# Module_Output_Connector.net
KiCad netlist of a schematic drawn in Altium Designer
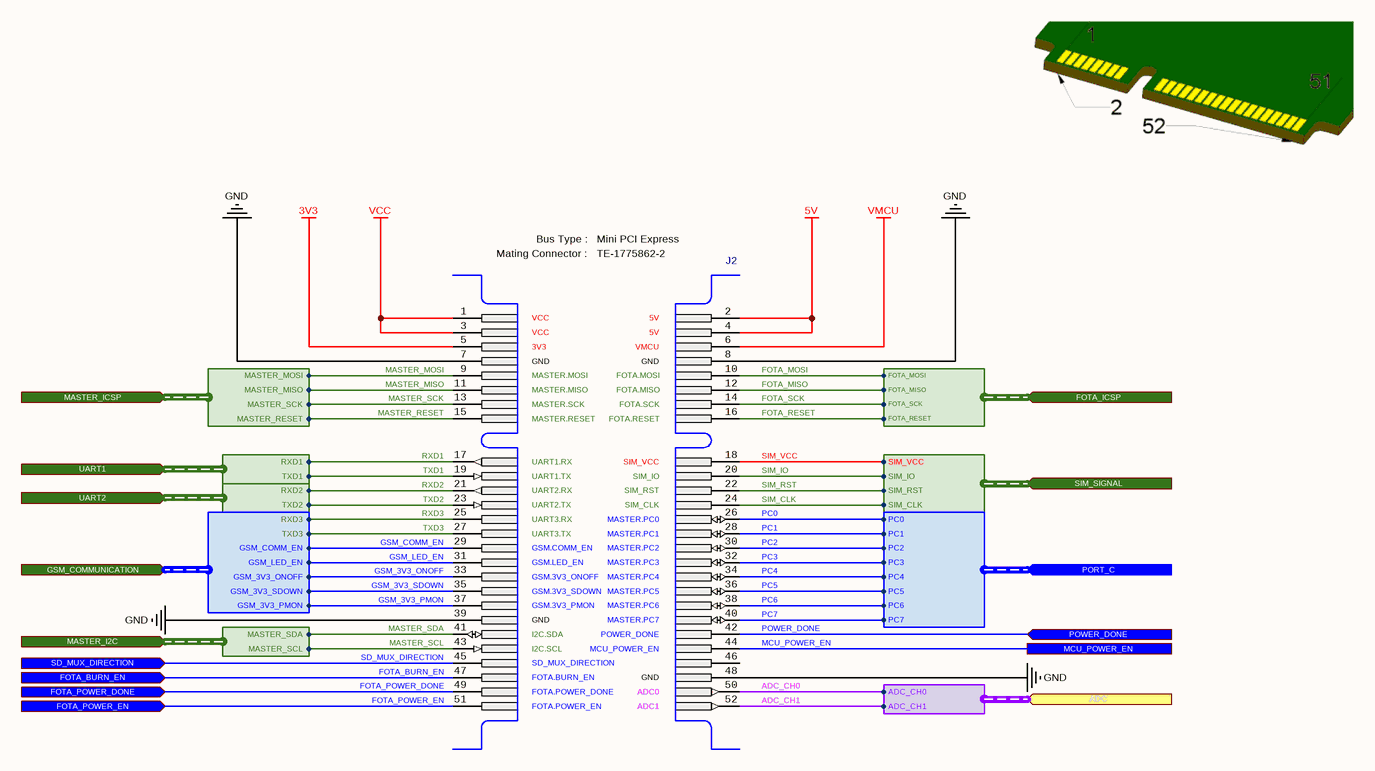
[diagram p0: Module Output Connector.SchDoc]

(export (version "E")
  (design (tool "Eeschema 10.0.6"))
  (components
    (comp (ref "J2")
      (value "Mini PCI Express Gold Finger")
      (footprint "PCB - Mini PCI Express")
      (fields (field (name "BUS TYPE") "Mini PCI Express") (field (name "MATING CONNECTOR") "TE-1775862-2"))
      (libsource (lib "Ovoo_Library") (part "PCB - Mini PCI Express & MSATA"))
    )
  )
  (nets
    (net (code "10") (name "/ADC_CH0") (class "Default")
      (node (ref "J2") (pin "50") (pinfunction "Pin-50_50") (pintype "output"))
    )
    (net (code "11") (name "/ADC_CH1") (class "Default")
      (node (ref "J2") (pin "52") (pinfunction "Pin-52_52") (pintype "output"))
    )
    (net (code "12") (name "/FOTA_BURN_EN") (class "Default")
      (node (ref "J2") (pin "47") (pinfunction "Pin-47_47") (pintype "passive"))
    )
    (net (code "13") (name "/FOTA_MISO") (class "Default")
      (node (ref "J2") (pin "12") (pinfunction "Pin-12_12") (pintype "passive"))
    )
    (net (code "14") (name "/FOTA_MOSI") (class "Default")
      (node (ref "J2") (pin "10") (pinfunction "Pin-10_10") (pintype "passive"))
    )
    (net (code "15") (name "/FOTA_POWER_DONE") (class "Default")
      (node (ref "J2") (pin "49") (pinfunction "Pin-49_49") (pintype "passive"))
    )
    (net (code "16") (name "/FOTA_POWER_EN") (class "Default")
      (node (ref "J2") (pin "51") (pinfunction "Pin-51_51") (pintype "passive"))
    )
    (net (code "17") (name "/FOTA_RESET") (class "Default")
      (node (ref "J2") (pin "16") (pinfunction "Pin-16_16") (pintype "passive"))
    )
    (net (code "18") (name "/FOTA_SCK") (class "Default")
      (node (ref "J2") (pin "14") (pinfunction "Pin-14_14") (pintype "passive"))
    )
    (net (code "19") (name "/GSM_3V3_ONOFF") (class "Default")
      (node (ref "J2") (pin "33") (pinfunction "Pin-33_33") (pintype "passive"))
    )
    (net (code "20") (name "/GSM_3V3_PMON") (class "Default")
      (node (ref "J2") (pin "37") (pinfunction "Pin-37_37") (pintype "passive"))
    )
    (net (code "21") (name "/GSM_3V3_SDOWN") (class "Default")
      (node (ref "J2") (pin "35") (pinfunction "Pin-35_35") (pintype "passive"))
    )
    (net (code "22") (name "/GSM_COMM_EN") (class "Default")
      (node (ref "J2") (pin "29") (pinfunction "Pin-29_29") (pintype "passive"))
    )
    (net (code "23") (name "/GSM_LED_EN") (class "Default")
      (node (ref "J2") (pin "31") (pinfunction "Pin-31_31") (pintype "passive"))
    )
    (net (code "24") (name "/MASTER_MISO") (class "Default")
      (node (ref "J2") (pin "11") (pinfunction "Pin-11_11") (pintype "passive"))
    )
    (net (code "25") (name "/MASTER_MOSI") (class "Default")
      (node (ref "J2") (pin "9") (pinfunction "Pin-9_9") (pintype "passive"))
    )
    (net (code "26") (name "/MASTER_RESET") (class "Default")
      (node (ref "J2") (pin "15") (pinfunction "Pin-15_15") (pintype "passive"))
    )
    (net (code "27") (name "/MASTER_SCK") (class "Default")
      (node (ref "J2") (pin "13") (pinfunction "Pin-13_13") (pintype "passive"))
    )
    (net (code "28") (name "/MASTER_SCL") (class "Default")
      (node (ref "J2") (pin "43") (pinfunction "Pin-43_43") (pintype "input"))
    )
    (net (code "29") (name "/MASTER_SDA") (class "Default")
      (node (ref "J2") (pin "41") (pinfunction "Pin-41_41") (pintype "bidirectional"))
    )
    (net (code "30") (name "/MCU_POWER_EN") (class "Default")
      (node (ref "J2") (pin "44") (pinfunction "Pin-44_44") (pintype "passive"))
    )
    (net (code "31") (name "/PC0") (class "Default")
      (node (ref "J2") (pin "26") (pinfunction "Pin-26_26") (pintype "bidirectional"))
    )
    (net (code "32") (name "/PC1") (class "Default")
      (node (ref "J2") (pin "28") (pinfunction "Pin-28_28") (pintype "bidirectional"))
    )
    (net (code "33") (name "/PC2") (class "Default")
      (node (ref "J2") (pin "30") (pinfunction "Pin-30_30") (pintype "bidirectional"))
    )
    (net (code "34") (name "/PC3") (class "Default")
      (node (ref "J2") (pin "32") (pinfunction "Pin-32_32") (pintype "bidirectional"))
    )
    (net (code "35") (name "/PC4") (class "Default")
      (node (ref "J2") (pin "34") (pinfunction "Pin-34_34") (pintype "bidirectional"))
    )
    (net (code "36") (name "/PC5") (class "Default")
      (node (ref "J2") (pin "36") (pinfunction "Pin-36_36") (pintype "bidirectional"))
    )
    (net (code "37") (name "/PC6") (class "Default")
      (node (ref "J2") (pin "38") (pinfunction "Pin-38_38") (pintype "bidirectional"))
    )
    (net (code "38") (name "/PC7") (class "Default")
      (node (ref "J2") (pin "40") (pinfunction "Pin-40_40") (pintype "bidirectional"))
    )
    (net (code "39") (name "/POWER_DONE") (class "Default")
      (node (ref "J2") (pin "42") (pinfunction "Pin-42_42") (pintype "passive"))
    )
    (net (code "40") (name "/RXD1") (class "Default")
      (node (ref "J2") (pin "17") (pinfunction "Pin-17_17") (pintype "output"))
    )
    (net (code "41") (name "/RXD2") (class "Default")
      (node (ref "J2") (pin "21") (pinfunction "Pin-21_21") (pintype "output"))
    )
    (net (code "42") (name "/RXD3") (class "Default")
      (node (ref "J2") (pin "25") (pinfunction "Pin-25_25") (pintype "passive"))
    )
    (net (code "43") (name "/SD_MUX_DIRECTION") (class "Default")
      (node (ref "J2") (pin "45") (pinfunction "Pin-45_45") (pintype "passive"))
    )
    (net (code "44") (name "/SIM_CLK") (class "Default")
      (node (ref "J2") (pin "24") (pinfunction "Pin-24_24") (pintype "passive"))
    )
    (net (code "45") (name "/SIM_IO") (class "Default")
      (node (ref "J2") (pin "20") (pinfunction "Pin-20_20") (pintype "passive"))
    )
    (net (code "46") (name "/SIM_RST") (class "Default")
      (node (ref "J2") (pin "22") (pinfunction "Pin-22_22") (pintype "passive"))
    )
    (net (code "48") (name "/SIM_VCC") (class "Default")
      (node (ref "J2") (pin "18") (pinfunction "Pin-18_18") (pintype "passive"))
    )
    (net (code "49") (name "/TXD1") (class "Default")
      (node (ref "J2") (pin "19") (pinfunction "Pin-19_19") (pintype "input"))
    )
    (net (code "50") (name "/TXD2") (class "Default")
      (node (ref "J2") (pin "23") (pinfunction "Pin-23_23") (pintype "input"))
    )
    (net (code "51") (name "/TXD3") (class "Default")
      (node (ref "J2") (pin "27") (pinfunction "Pin-27_27") (pintype "passive"))
    )
    (net (code "60") (name "3V3") (class "Default")
      (node (ref "J2") (pin "5") (pinfunction "Pin-5_5") (pintype "passive"))
    )
    (net (code "61") (name "5V") (class "Default")
      (node (ref "J2") (pin "2") (pinfunction "Pin-2_2") (pintype "passive"))
      (node (ref "J2") (pin "4") (pinfunction "Pin-4_4") (pintype "passive"))
    )
    (net (code "62") (name "GND") (class "Default")
      (node (ref "J2") (pin "39") (pinfunction "Pin-39_39") (pintype "passive"))
      (node (ref "J2") (pin "48") (pinfunction "Pin-48_48") (pintype "passive"))
      (node (ref "J2") (pin "7") (pinfunction "Pin-7_7") (pintype "passive"))
      (node (ref "J2") (pin "8") (pinfunction "Pin-8_8") (pintype "passive"))
    )
    (net (code "63") (name "VCC") (class "Default")
      (node (ref "J2") (pin "1") (pinfunction "Pin-1_1") (pintype "passive"))
      (node (ref "J2") (pin "3") (pinfunction "Pin-3_3") (pintype "passive"))
    )
    (net (code "64") (name "VMCU") (class "Default")
      (node (ref "J2") (pin "6") (pinfunction "Pin-6_6") (pintype "passive"))
    )
    (net (code "65") (name "unconnected-(J2-Pin-46-Pad46)") (class "Default")
      (node (ref "J2") (pin "46") (pinfunction "Pin-46_46") (pintype "passive"))
    )
  )
)
